# M960-1.net
KiCad netlist of a schematic drawn in EAGLE
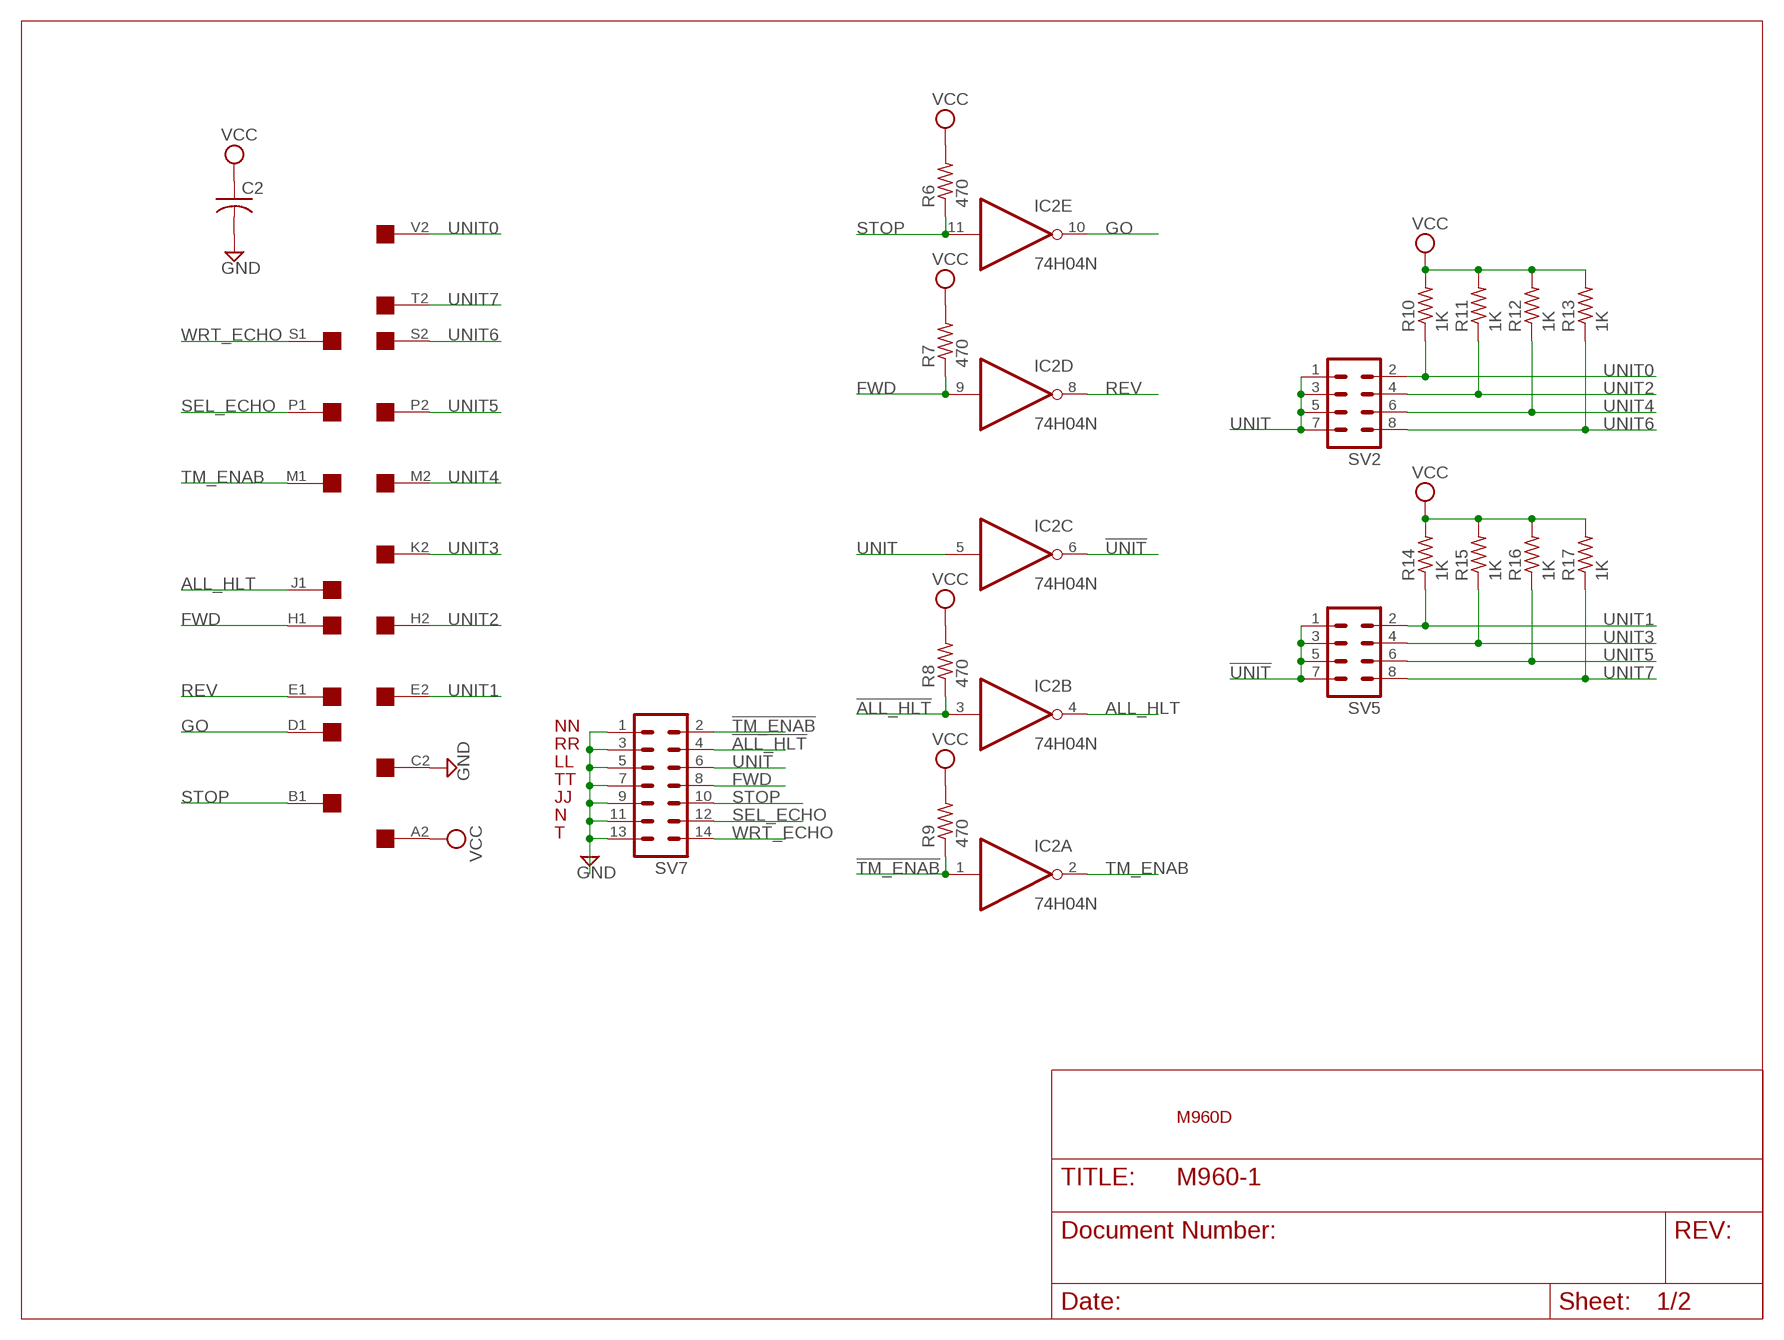
[diagram p0: schematic, sheet 1]
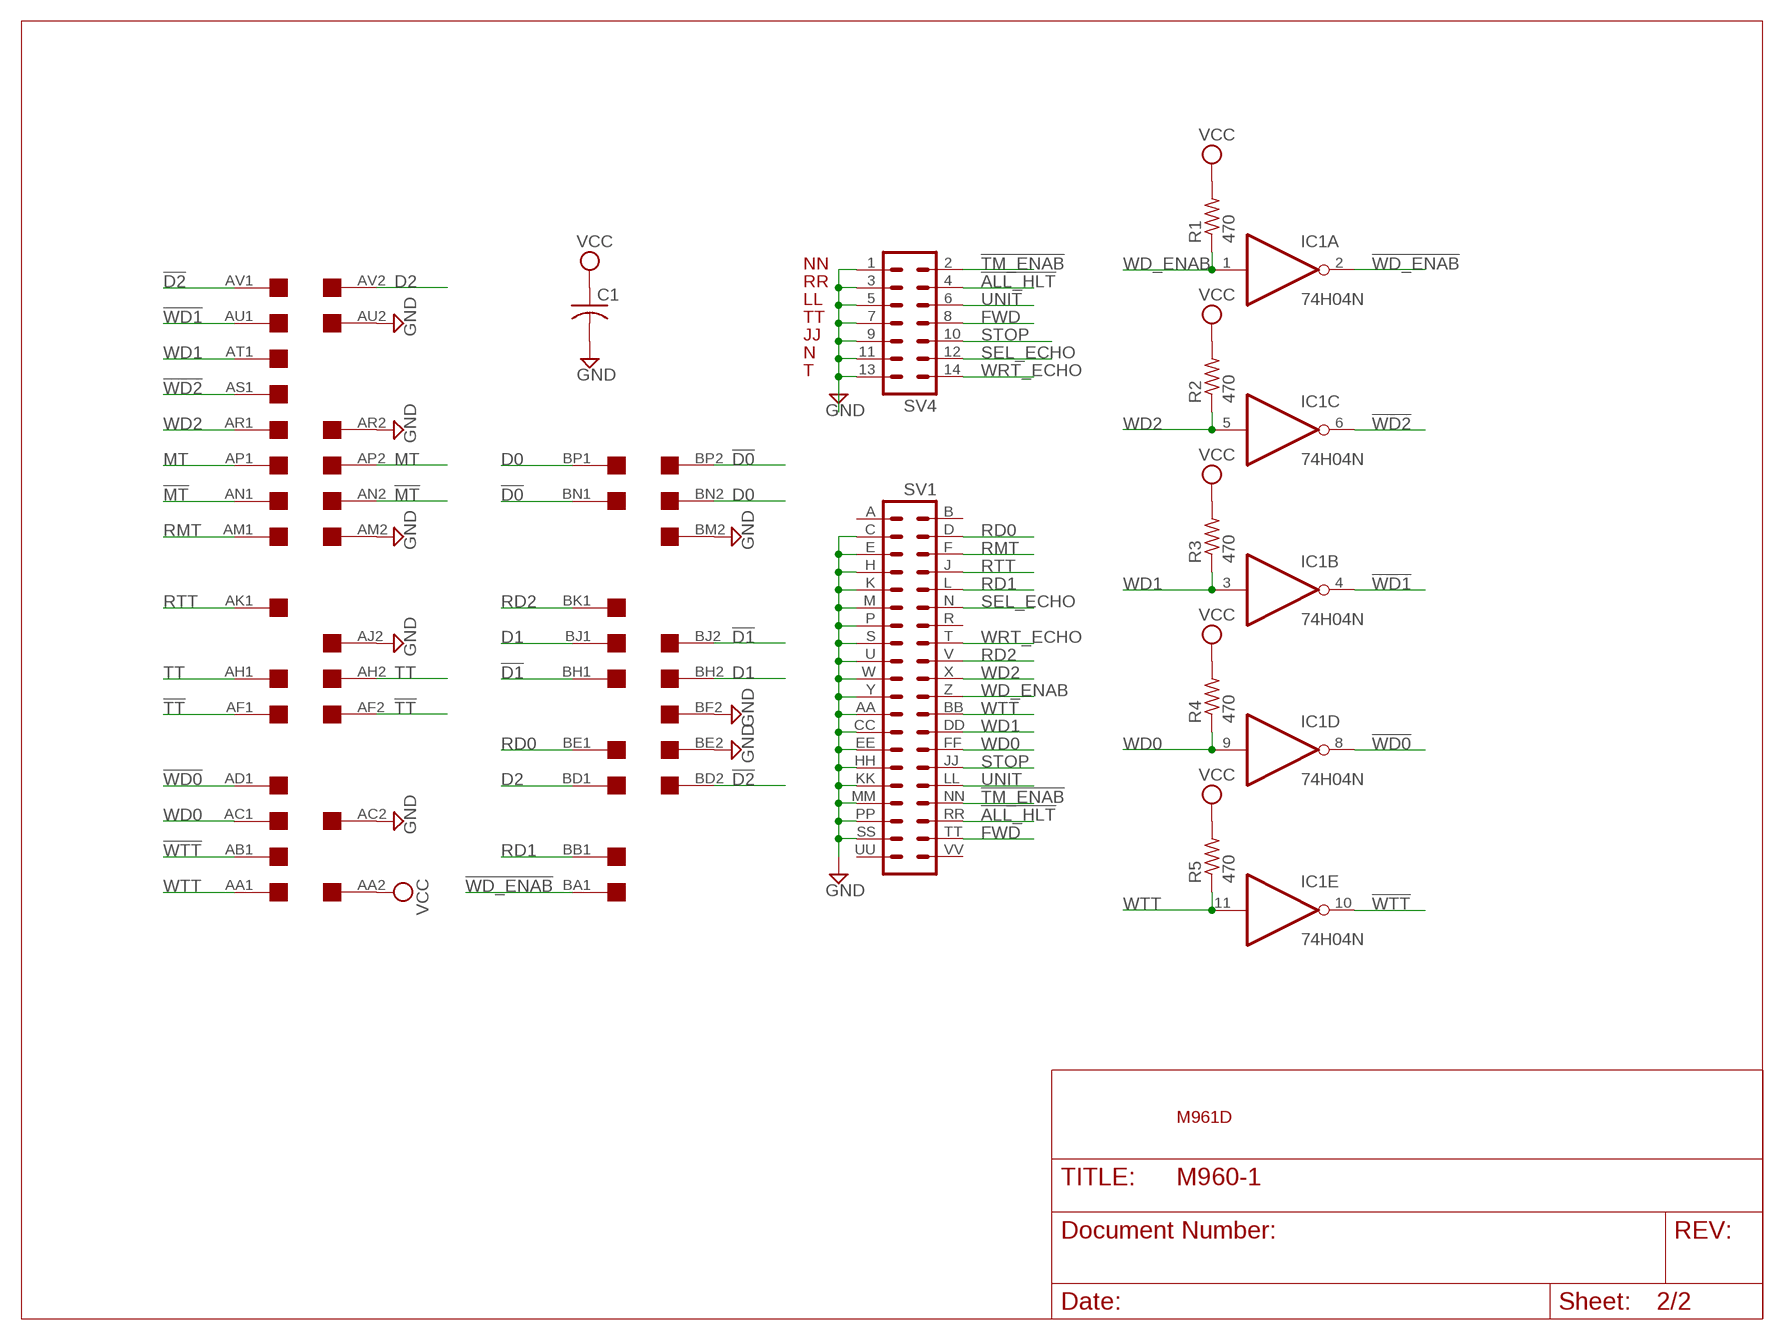
[diagram p1: schematic, sheet 2]

(export (version "E")
  (design (tool "Eeschema 10.0.6"))
  (components
    (comp (ref "C2")
      (value "C-US050-025X075")
      (footprint "eagle-import:C050-025X075")
      (libsource (lib "eagle-import") (part "C-US050-025X075"))
    )
    (comp (ref "IC2")
      (value "74H04N")
      (footprint "eagle-import:DIL14")
      (libsource (lib "eagle-import") (part "7404N"))
    )
    (comp (ref "R6")
      (value "470")
      (footprint "eagle-import:0207_10")
      (libsource (lib "eagle-import") (part "R-US_0207/10"))
    )
    (comp (ref "R7")
      (value "470")
      (footprint "eagle-import:0207_10")
      (libsource (lib "eagle-import") (part "R-US_0207/10"))
    )
    (comp (ref "R8")
      (value "470")
      (footprint "eagle-import:0207_10")
      (libsource (lib "eagle-import") (part "R-US_0207/10"))
    )
    (comp (ref "R9")
      (value "470")
      (footprint "eagle-import:0207_10")
      (libsource (lib "eagle-import") (part "R-US_0207/10"))
    )
    (comp (ref "R10")
      (value "1K")
      (footprint "eagle-import:0207_10")
      (libsource (lib "eagle-import") (part "R-US_0207/10"))
    )
    (comp (ref "R11")
      (value "1K")
      (footprint "eagle-import:0207_10")
      (libsource (lib "eagle-import") (part "R-US_0207/10"))
    )
    (comp (ref "R12")
      (value "1K")
      (footprint "eagle-import:0207_10")
      (libsource (lib "eagle-import") (part "R-US_0207/10"))
    )
    (comp (ref "R13")
      (value "1K")
      (footprint "eagle-import:0207_10")
      (libsource (lib "eagle-import") (part "R-US_0207/10"))
    )
    (comp (ref "R14")
      (value "1K")
      (footprint "eagle-import:0207_10")
      (libsource (lib "eagle-import") (part "R-US_0207/10"))
    )
    (comp (ref "R15")
      (value "1K")
      (footprint "eagle-import:0207_10")
      (libsource (lib "eagle-import") (part "R-US_0207/10"))
    )
    (comp (ref "R16")
      (value "1K")
      (footprint "eagle-import:0207_10")
      (libsource (lib "eagle-import") (part "R-US_0207/10"))
    )
    (comp (ref "R17")
      (value "1K")
      (footprint "eagle-import:0207_10")
      (libsource (lib "eagle-import") (part "R-US_0207/10"))
    )
    (comp (ref "SV2")
      (value "MA04-2")
      (footprint "eagle-import:MA04-2")
      (libsource (lib "eagle-import") (part "MA04-2"))
    )
    (comp (ref "SV5")
      (value "MA04-2")
      (footprint "eagle-import:MA04-2")
      (libsource (lib "eagle-import") (part "MA04-2"))
    )
    (comp (ref "SV7")
      (value "MA07-2")
      (footprint "eagle-import:MA07-2")
      (libsource (lib "eagle-import") (part "MA07-2"))
    )
    (comp (ref "U$3")
      (value "SINGLE")
      (footprint "eagle-import:EDGE-CON2")
      (libsource (lib "eagle-import") (part "SINGLE"))
    )
    (comp (ref "C1")
      (value "C-US050-025X075")
      (footprint "eagle-import:C050-025X075")
      (libsource (lib "eagle-import") (part "C-US050-025X075"))
    )
    (comp (ref "EDGE$1")
      (value "DOUBLE")
      (footprint "eagle-import:EDGE-CON4")
      (libsource (lib "eagle-import") (part "DOUBLE"))
    )
    (comp (ref "IC1")
      (value "74H04N")
      (footprint "eagle-import:DIL14")
      (libsource (lib "eagle-import") (part "7404N"))
    )
    (comp (ref "R1")
      (value "470")
      (footprint "eagle-import:0207_10")
      (libsource (lib "eagle-import") (part "R-US_0207/10"))
    )
    (comp (ref "R2")
      (value "470")
      (footprint "eagle-import:0207_10")
      (libsource (lib "eagle-import") (part "R-US_0207/10"))
    )
    (comp (ref "R3")
      (value "470")
      (footprint "eagle-import:0207_10")
      (libsource (lib "eagle-import") (part "R-US_0207/10"))
    )
    (comp (ref "R4")
      (value "470")
      (footprint "eagle-import:0207_10")
      (libsource (lib "eagle-import") (part "R-US_0207/10"))
    )
    (comp (ref "R5")
      (value "470")
      (footprint "eagle-import:0207_10")
      (libsource (lib "eagle-import") (part "R-US_0207/10"))
    )
    (comp (ref "SV1")
      (value "DEC40PINV")
      (footprint "eagle-import:DEC40PINV")
      (libsource (lib "eagle-import") (part "DEC40PINV"))
    )
    (comp (ref "SV4")
      (value "MA07-2")
      (footprint "eagle-import:MA07-2")
      (libsource (lib "eagle-import") (part "MA07-2"))
    )
  )
  (nets
    (net (code "1") (name "ALL_HLT") (class "Default")
      (node (ref "IC2") (pin "4") (pinfunction "O_4") (pintype "output"))
      (node (ref "U$3") (pin "J1") (pinfunction "1_J1") (pintype "bidirectional"))
    )
    (net (code "2") (name "D0") (class "Default")
      (node (ref "EDGE$1") (pin "BN2") (pinfunction "1_BN2") (pintype "bidirectional"))
      (node (ref "EDGE$1") (pin "BP1") (pinfunction "1_BP1") (pintype "bidirectional"))
    )
    (net (code "3") (name "D1") (class "Default")
      (node (ref "EDGE$1") (pin "BH2") (pinfunction "1_BH2") (pintype "bidirectional"))
      (node (ref "EDGE$1") (pin "BJ1") (pinfunction "1_BJ1") (pintype "bidirectional"))
    )
    (net (code "4") (name "D2") (class "Default")
      (node (ref "EDGE$1") (pin "AV2") (pinfunction "1_AV2") (pintype "bidirectional"))
      (node (ref "EDGE$1") (pin "BD1") (pinfunction "1_BD1") (pintype "bidirectional"))
    )
    (net (code "5") (name "FWD") (class "Default")
      (node (ref "IC2") (pin "9") (pinfunction "I_9") (pintype "input"))
      (node (ref "R7") (pin "1") (pinfunction "1_1") (pintype "passive"))
      (node (ref "SV1") (pin "TT") (pinfunction "38_TT") (pintype "bidirectional"))
      (node (ref "SV4") (pin "8") (pinfunction "8_8") (pintype "passive"))
      (node (ref "SV7") (pin "8") (pinfunction "8_8") (pintype "passive"))
      (node (ref "U$3") (pin "H1") (pinfunction "1_H1") (pintype "bidirectional"))
    )
    (net (code "6") (name "GND") (class "Default")
      (node (ref "C1") (pin "2") (pinfunction "2_2") (pintype "passive"))
      (node (ref "C2") (pin "2") (pinfunction "2_2") (pintype "passive"))
      (node (ref "EDGE$1") (pin "AC2") (pinfunction "1_AC2") (pintype "bidirectional"))
      (node (ref "EDGE$1") (pin "AJ2") (pinfunction "1_AJ2") (pintype "bidirectional"))
      (node (ref "EDGE$1") (pin "AM2") (pinfunction "1_AM2") (pintype "bidirectional"))
      (node (ref "EDGE$1") (pin "AR2") (pinfunction "1_AR2") (pintype "bidirectional"))
      (node (ref "EDGE$1") (pin "AU2") (pinfunction "1_AU2") (pintype "bidirectional"))
      (node (ref "EDGE$1") (pin "BE2") (pinfunction "1_BE2") (pintype "bidirectional"))
      (node (ref "EDGE$1") (pin "BF2") (pinfunction "1_BF2") (pintype "bidirectional"))
      (node (ref "EDGE$1") (pin "BM2") (pinfunction "1_BM2") (pintype "bidirectional"))
      (node (ref "SV1") (pin "AA") (pinfunction "23_AA") (pintype "bidirectional"))
      (node (ref "SV1") (pin "C") (pinfunction "3_C") (pintype "bidirectional"))
      (node (ref "SV1") (pin "CC") (pinfunction "25_CC") (pintype "bidirectional"))
      (node (ref "SV1") (pin "E") (pinfunction "5_E") (pintype "bidirectional"))
      (node (ref "SV1") (pin "EE") (pinfunction "27_EE") (pintype "bidirectional"))
      (node (ref "SV1") (pin "H") (pinfunction "7_H") (pintype "bidirectional"))
      (node (ref "SV1") (pin "HH") (pinfunction "29_HH") (pintype "bidirectional"))
      (node (ref "SV1") (pin "K") (pinfunction "9_K") (pintype "bidirectional"))
      (node (ref "SV1") (pin "KK") (pinfunction "31_KK") (pintype "bidirectional"))
      (node (ref "SV1") (pin "M") (pinfunction "11_M") (pintype "bidirectional"))
      (node (ref "SV1") (pin "MM") (pinfunction "33_MM") (pintype "bidirectional"))
      (node (ref "SV1") (pin "P") (pinfunction "13_P") (pintype "bidirectional"))
      (node (ref "SV1") (pin "PP") (pinfunction "35_PP") (pintype "bidirectional"))
      (node (ref "SV1") (pin "S") (pinfunction "15_S") (pintype "bidirectional"))
      (node (ref "SV1") (pin "SS") (pinfunction "37_SS") (pintype "bidirectional"))
      (node (ref "SV1") (pin "U") (pinfunction "17_U") (pintype "bidirectional"))
      (node (ref "SV1") (pin "W") (pinfunction "19_W") (pintype "bidirectional"))
      (node (ref "SV1") (pin "Y") (pinfunction "21_Y") (pintype "bidirectional"))
      (node (ref "SV4") (pin "1") (pinfunction "1_1") (pintype "passive"))
      (node (ref "SV4") (pin "11") (pinfunction "11_11") (pintype "passive"))
      (node (ref "SV4") (pin "13") (pinfunction "13_13") (pintype "passive"))
      (node (ref "SV4") (pin "3") (pinfunction "3_3") (pintype "passive"))
      (node (ref "SV4") (pin "5") (pinfunction "5_5") (pintype "passive"))
      (node (ref "SV4") (pin "7") (pinfunction "7_7") (pintype "passive"))
      (node (ref "SV4") (pin "9") (pinfunction "9_9") (pintype "passive"))
      (node (ref "SV7") (pin "1") (pinfunction "1_1") (pintype "passive"))
      (node (ref "SV7") (pin "11") (pinfunction "11_11") (pintype "passive"))
      (node (ref "SV7") (pin "13") (pinfunction "13_13") (pintype "passive"))
      (node (ref "SV7") (pin "3") (pinfunction "3_3") (pintype "passive"))
      (node (ref "SV7") (pin "5") (pinfunction "5_5") (pintype "passive"))
      (node (ref "SV7") (pin "7") (pinfunction "7_7") (pintype "passive"))
      (node (ref "SV7") (pin "9") (pinfunction "9_9") (pintype "passive"))
      (node (ref "U$3") (pin "C2") (pinfunction "1_C2") (pintype "bidirectional"))
    )
    (net (code "7") (name "GO") (class "Default")
      (node (ref "IC2") (pin "10") (pinfunction "O_10") (pintype "output"))
      (node (ref "U$3") (pin "D1") (pinfunction "1_D1") (pintype "bidirectional"))
    )
    (net (code "8") (name "MT") (class "Default")
      (node (ref "EDGE$1") (pin "AP1") (pinfunction "1_AP1") (pintype "bidirectional"))
      (node (ref "EDGE$1") (pin "AP2") (pinfunction "1_AP2") (pintype "bidirectional"))
    )
    (net (code "9") (name "RD0") (class "Default")
      (node (ref "EDGE$1") (pin "BE1") (pinfunction "1_BE1") (pintype "bidirectional"))
      (node (ref "SV1") (pin "D") (pinfunction "4_D") (pintype "bidirectional"))
    )
    (net (code "10") (name "RD1") (class "Default")
      (node (ref "EDGE$1") (pin "BB1") (pinfunction "1_BB1") (pintype "bidirectional"))
      (node (ref "SV1") (pin "L") (pinfunction "10_L") (pintype "bidirectional"))
    )
    (net (code "11") (name "RD2") (class "Default")
      (node (ref "EDGE$1") (pin "BK1") (pinfunction "1_BK1") (pintype "bidirectional"))
      (node (ref "SV1") (pin "V") (pinfunction "18_V") (pintype "bidirectional"))
    )
    (net (code "12") (name "REV") (class "Default")
      (node (ref "IC2") (pin "8") (pinfunction "O_8") (pintype "output"))
      (node (ref "U$3") (pin "E1") (pinfunction "1_E1") (pintype "bidirectional"))
    )
    (net (code "13") (name "RMT") (class "Default")
      (node (ref "EDGE$1") (pin "AM1") (pinfunction "1_AM1") (pintype "bidirectional"))
      (node (ref "SV1") (pin "F") (pinfunction "6_F") (pintype "bidirectional"))
    )
    (net (code "14") (name "RTT") (class "Default")
      (node (ref "EDGE$1") (pin "AK1") (pinfunction "1_AK1") (pintype "bidirectional"))
      (node (ref "SV1") (pin "J") (pinfunction "8_J") (pintype "bidirectional"))
    )
    (net (code "15") (name "SEL_ECHO") (class "Default")
      (node (ref "SV1") (pin "N") (pinfunction "12_N") (pintype "bidirectional"))
      (node (ref "SV4") (pin "12") (pinfunction "12_12") (pintype "passive"))
      (node (ref "SV7") (pin "12") (pinfunction "12_12") (pintype "passive"))
      (node (ref "U$3") (pin "P1") (pinfunction "1_P1") (pintype "bidirectional"))
    )
    (net (code "16") (name "STOP") (class "Default")
      (node (ref "IC2") (pin "11") (pinfunction "I_11") (pintype "input"))
      (node (ref "R6") (pin "1") (pinfunction "1_1") (pintype "passive"))
      (node (ref "SV1") (pin "JJ") (pinfunction "30_JJ") (pintype "bidirectional"))
      (node (ref "SV4") (pin "10") (pinfunction "10_10") (pintype "passive"))
      (node (ref "SV7") (pin "10") (pinfunction "10_10") (pintype "passive"))
      (node (ref "U$3") (pin "B1") (pinfunction "1_B1") (pintype "bidirectional"))
    )
    (net (code "17") (name "TM_ENAB") (class "Default")
      (node (ref "IC2") (pin "2") (pinfunction "O_2") (pintype "output"))
      (node (ref "U$3") (pin "M1") (pinfunction "1_M1") (pintype "bidirectional"))
    )
    (net (code "18") (name "TT") (class "Default")
      (node (ref "EDGE$1") (pin "AH1") (pinfunction "1_AH1") (pintype "bidirectional"))
      (node (ref "EDGE$1") (pin "AH2") (pinfunction "1_AH2") (pintype "bidirectional"))
    )
    (net (code "19") (name "UNIT") (class "Default")
      (node (ref "IC2") (pin "5") (pinfunction "I_5") (pintype "input"))
      (node (ref "SV1") (pin "LL") (pinfunction "32_LL") (pintype "bidirectional"))
      (node (ref "SV2") (pin "1") (pinfunction "1_1") (pintype "passive"))
      (node (ref "SV2") (pin "3") (pinfunction "3_3") (pintype "passive"))
      (node (ref "SV2") (pin "5") (pinfunction "5_5") (pintype "passive"))
      (node (ref "SV2") (pin "7") (pinfunction "7_7") (pintype "passive"))
      (node (ref "SV4") (pin "6") (pinfunction "6_6") (pintype "passive"))
      (node (ref "SV7") (pin "6") (pinfunction "6_6") (pintype "passive"))
    )
    (net (code "20") (name "UNIT0") (class "Default")
      (node (ref "R10") (pin "1") (pinfunction "1_1") (pintype "passive"))
      (node (ref "SV2") (pin "2") (pinfunction "2_2") (pintype "passive"))
      (node (ref "U$3") (pin "V2") (pinfunction "1_V2") (pintype "bidirectional"))
    )
    (net (code "21") (name "UNIT1") (class "Default")
      (node (ref "R14") (pin "1") (pinfunction "1_1") (pintype "passive"))
      (node (ref "SV5") (pin "2") (pinfunction "2_2") (pintype "passive"))
      (node (ref "U$3") (pin "E2") (pinfunction "1_E2") (pintype "bidirectional"))
    )
    (net (code "22") (name "UNIT2") (class "Default")
      (node (ref "R11") (pin "1") (pinfunction "1_1") (pintype "passive"))
      (node (ref "SV2") (pin "4") (pinfunction "4_4") (pintype "passive"))
      (node (ref "U$3") (pin "H2") (pinfunction "1_H2") (pintype "bidirectional"))
    )
    (net (code "23") (name "UNIT3") (class "Default")
      (node (ref "R15") (pin "1") (pinfunction "1_1") (pintype "passive"))
      (node (ref "SV5") (pin "4") (pinfunction "4_4") (pintype "passive"))
      (node (ref "U$3") (pin "K2") (pinfunction "1_K2") (pintype "bidirectional"))
    )
    (net (code "24") (name "UNIT4") (class "Default")
      (node (ref "R12") (pin "1") (pinfunction "1_1") (pintype "passive"))
      (node (ref "SV2") (pin "6") (pinfunction "6_6") (pintype "passive"))
      (node (ref "U$3") (pin "M2") (pinfunction "1_M2") (pintype "bidirectional"))
    )
    (net (code "25") (name "UNIT5") (class "Default")
      (node (ref "R16") (pin "1") (pinfunction "1_1") (pintype "passive"))
      (node (ref "SV5") (pin "6") (pinfunction "6_6") (pintype "passive"))
      (node (ref "U$3") (pin "P2") (pinfunction "1_P2") (pintype "bidirectional"))
    )
    (net (code "26") (name "UNIT6") (class "Default")
      (node (ref "R13") (pin "1") (pinfunction "1_1") (pintype "passive"))
      (node (ref "SV2") (pin "8") (pinfunction "8_8") (pintype "passive"))
      (node (ref "U$3") (pin "S2") (pinfunction "1_S2") (pintype "bidirectional"))
    )
    (net (code "27") (name "UNIT7") (class "Default")
      (node (ref "R17") (pin "1") (pinfunction "1_1") (pintype "passive"))
      (node (ref "SV5") (pin "8") (pinfunction "8_8") (pintype "passive"))
      (node (ref "U$3") (pin "T2") (pinfunction "1_T2") (pintype "bidirectional"))
    )
    (net (code "28") (name "VCC") (class "Default")
      (node (ref "C1") (pin "1") (pinfunction "1_1") (pintype "passive"))
      (node (ref "C2") (pin "1") (pinfunction "1_1") (pintype "passive"))
      (node (ref "EDGE$1") (pin "AA2") (pinfunction "1_AA2") (pintype "bidirectional"))
      (node (ref "R1") (pin "2") (pinfunction "2_2") (pintype "passive"))
      (node (ref "R10") (pin "2") (pinfunction "2_2") (pintype "passive"))
      (node (ref "R11") (pin "2") (pinfunction "2_2") (pintype "passive"))
      (node (ref "R12") (pin "2") (pinfunction "2_2") (pintype "passive"))
      (node (ref "R13") (pin "2") (pinfunction "2_2") (pintype "passive"))
      (node (ref "R14") (pin "2") (pinfunction "2_2") (pintype "passive"))
      (node (ref "R15") (pin "2") (pinfunction "2_2") (pintype "passive"))
      (node (ref "R16") (pin "2") (pinfunction "2_2") (pintype "passive"))
      (node (ref "R17") (pin "2") (pinfunction "2_2") (pintype "passive"))
      (node (ref "R2") (pin "2") (pinfunction "2_2") (pintype "passive"))
      (node (ref "R3") (pin "2") (pinfunction "2_2") (pintype "passive"))
      (node (ref "R4") (pin "2") (pinfunction "2_2") (pintype "passive"))
      (node (ref "R5") (pin "2") (pinfunction "2_2") (pintype "passive"))
      (node (ref "R6") (pin "2") (pinfunction "2_2") (pintype "passive"))
      (node (ref "R7") (pin "2") (pinfunction "2_2") (pintype "passive"))
      (node (ref "R8") (pin "2") (pinfunction "2_2") (pintype "passive"))
      (node (ref "R9") (pin "2") (pinfunction "2_2") (pintype "passive"))
      (node (ref "U$3") (pin "A2") (pinfunction "1_A2") (pintype "bidirectional"))
    )
    (net (code "29") (name "WD0") (class "Default")
      (node (ref "EDGE$1") (pin "AC1") (pinfunction "1_AC1") (pintype "bidirectional"))
      (node (ref "IC1") (pin "9") (pinfunction "I_9") (pintype "input"))
      (node (ref "R4") (pin "1") (pinfunction "1_1") (pintype "passive"))
      (node (ref "SV1") (pin "FF") (pinfunction "28_FF") (pintype "bidirectional"))
    )
    (net (code "30") (name "WD1") (class "Default")
      (node (ref "EDGE$1") (pin "AT1") (pinfunction "1_AT1") (pintype "bidirectional"))
      (node (ref "IC1") (pin "3") (pinfunction "I_3") (pintype "input"))
      (node (ref "R3") (pin "1") (pinfunction "1_1") (pintype "passive"))
      (node (ref "SV1") (pin "DD") (pinfunction "26_DD") (pintype "bidirectional"))
    )
    (net (code "31") (name "WD2") (class "Default")
      (node (ref "EDGE$1") (pin "AR1") (pinfunction "1_AR1") (pintype "bidirectional"))
      (node (ref "IC1") (pin "5") (pinfunction "I_5") (pintype "input"))
      (node (ref "R2") (pin "1") (pinfunction "1_1") (pintype "passive"))
      (node (ref "SV1") (pin "X") (pinfunction "20_X") (pintype "bidirectional"))
    )
    (net (code "32") (name "WD_ENAB") (class "Default")
      (node (ref "IC1") (pin "1") (pinfunction "I_1") (pintype "input"))
      (node (ref "R1") (pin "1") (pinfunction "1_1") (pintype "passive"))
      (node (ref "SV1") (pin "Z") (pinfunction "22_Z") (pintype "bidirectional"))
    )
    (net (code "33") (name "WRT_ECHO") (class "Default")
      (node (ref "SV1") (pin "T") (pinfunction "16_T") (pintype "bidirectional"))
      (node (ref "SV4") (pin "14") (pinfunction "14_14") (pintype "passive"))
      (node (ref "SV7") (pin "14") (pinfunction "14_14") (pintype "passive"))
      (node (ref "U$3") (pin "S1") (pinfunction "1_S1") (pintype "bidirectional"))
    )
    (net (code "34") (name "WTT") (class "Default")
      (node (ref "EDGE$1") (pin "AA1") (pinfunction "1_AA1") (pintype "bidirectional"))
      (node (ref "IC1") (pin "11") (pinfunction "I_11") (pintype "input"))
      (node (ref "R5") (pin "1") (pinfunction "1_1") (pintype "passive"))
      (node (ref "SV1") (pin "BB") (pinfunction "24_BB") (pintype "bidirectional"))
    )
    (net (code "35") (name "unconnected-(SV1-1-PadA)") (class "Default")
      (node (ref "SV1") (pin "A") (pinfunction "1_A") (pintype "bidirectional"))
    )
    (net (code "36") (name "unconnected-(SV1-2-PadB)") (class "Default")
      (node (ref "SV1") (pin "B") (pinfunction "2_B") (pintype "bidirectional"))
    )
    (net (code "37") (name "unconnected-(SV1-14-PadR)") (class "Default")
      (node (ref "SV1") (pin "R") (pinfunction "14_R") (pintype "bidirectional"))
    )
    (net (code "38") (name "unconnected-(SV1-39-PadUU)") (class "Default")
      (node (ref "SV1") (pin "UU") (pinfunction "39_UU") (pintype "bidirectional"))
    )
    (net (code "39") (name "unconnected-(SV1-40-PadVV)") (class "Default")
      (node (ref "SV1") (pin "VV") (pinfunction "40_VV") (pintype "bidirectional"))
    )
    (net (code "40") (name "~{ALL_HLT}") (class "Default")
      (node (ref "IC2") (pin "3") (pinfunction "I_3") (pintype "input"))
      (node (ref "R8") (pin "1") (pinfunction "1_1") (pintype "passive"))
      (node (ref "SV1") (pin "RR") (pinfunction "36_RR") (pintype "bidirectional"))
      (node (ref "SV4") (pin "4") (pinfunction "4_4") (pintype "passive"))
      (node (ref "SV7") (pin "4") (pinfunction "4_4") (pintype "passive"))
    )
    (net (code "41") (name "~{D0}") (class "Default")
      (node (ref "EDGE$1") (pin "BN1") (pinfunction "1_BN1") (pintype "bidirectional"))
      (node (ref "EDGE$1") (pin "BP2") (pinfunction "1_BP2") (pintype "bidirectional"))
    )
    (net (code "42") (name "~{D1}") (class "Default")
      (node (ref "EDGE$1") (pin "BH1") (pinfunction "1_BH1") (pintype "bidirectional"))
      (node (ref "EDGE$1") (pin "BJ2") (pinfunction "1_BJ2") (pintype "bidirectional"))
    )
    (net (code "43") (name "~{D2}") (class "Default")
      (node (ref "EDGE$1") (pin "AV1") (pinfunction "1_AV1") (pintype "bidirectional"))
      (node (ref "EDGE$1") (pin "BD2") (pinfunction "1_BD2") (pintype "bidirectional"))
    )
    (net (code "44") (name "~{MT}") (class "Default")
      (node (ref "EDGE$1") (pin "AN1") (pinfunction "1_AN1") (pintype "bidirectional"))
      (node (ref "EDGE$1") (pin "AN2") (pinfunction "1_AN2") (pintype "bidirectional"))
    )
    (net (code "45") (name "~{TM_ENAB}") (class "Default")
      (node (ref "IC2") (pin "1") (pinfunction "I_1") (pintype "input"))
      (node (ref "R9") (pin "1") (pinfunction "1_1") (pintype "passive"))
      (node (ref "SV1") (pin "NN") (pinfunction "34_NN") (pintype "bidirectional"))
      (node (ref "SV4") (pin "2") (pinfunction "2_2") (pintype "passive"))
      (node (ref "SV7") (pin "2") (pinfunction "2_2") (pintype "passive"))
    )
    (net (code "46") (name "~{TT}") (class "Default")
      (node (ref "EDGE$1") (pin "AF1") (pinfunction "1_AF1") (pintype "bidirectional"))
      (node (ref "EDGE$1") (pin "AF2") (pinfunction "1_AF2") (pintype "bidirectional"))
    )
    (net (code "47") (name "~{UNIT}") (class "Default")
      (node (ref "IC2") (pin "6") (pinfunction "O_6") (pintype "output"))
      (node (ref "SV5") (pin "1") (pinfunction "1_1") (pintype "passive"))
      (node (ref "SV5") (pin "3") (pinfunction "3_3") (pintype "passive"))
      (node (ref "SV5") (pin "5") (pinfunction "5_5") (pintype "passive"))
      (node (ref "SV5") (pin "7") (pinfunction "7_7") (pintype "passive"))
    )
    (net (code "48") (name "~{WD0}") (class "Default")
      (node (ref "EDGE$1") (pin "AD1") (pinfunction "1_AD1") (pintype "bidirectional"))
      (node (ref "IC1") (pin "8") (pinfunction "O_8") (pintype "output"))
    )
    (net (code "49") (name "~{WD1}") (class "Default")
      (node (ref "EDGE$1") (pin "AU1") (pinfunction "1_AU1") (pintype "bidirectional"))
      (node (ref "IC1") (pin "4") (pinfunction "O_4") (pintype "output"))
    )
    (net (code "50") (name "~{WD2}") (class "Default")
      (node (ref "EDGE$1") (pin "AS1") (pinfunction "1_AS1") (pintype "bidirectional"))
      (node (ref "IC1") (pin "6") (pinfunction "O_6") (pintype "output"))
    )
    (net (code "51") (name "~{WD_ENAB}") (class "Default")
      (node (ref "EDGE$1") (pin "BA1") (pinfunction "1_BA1") (pintype "bidirectional"))
      (node (ref "IC1") (pin "2") (pinfunction "O_2") (pintype "output"))
    )
    (net (code "52") (name "~{WTT}") (class "Default")
      (node (ref "EDGE$1") (pin "AB1") (pinfunction "1_AB1") (pintype "bidirectional"))
      (node (ref "IC1") (pin "10") (pinfunction "O_10") (pintype "output"))
    )
  )
)
